# MCU.net
KiCad netlist of a schematic drawn in Altium Designer
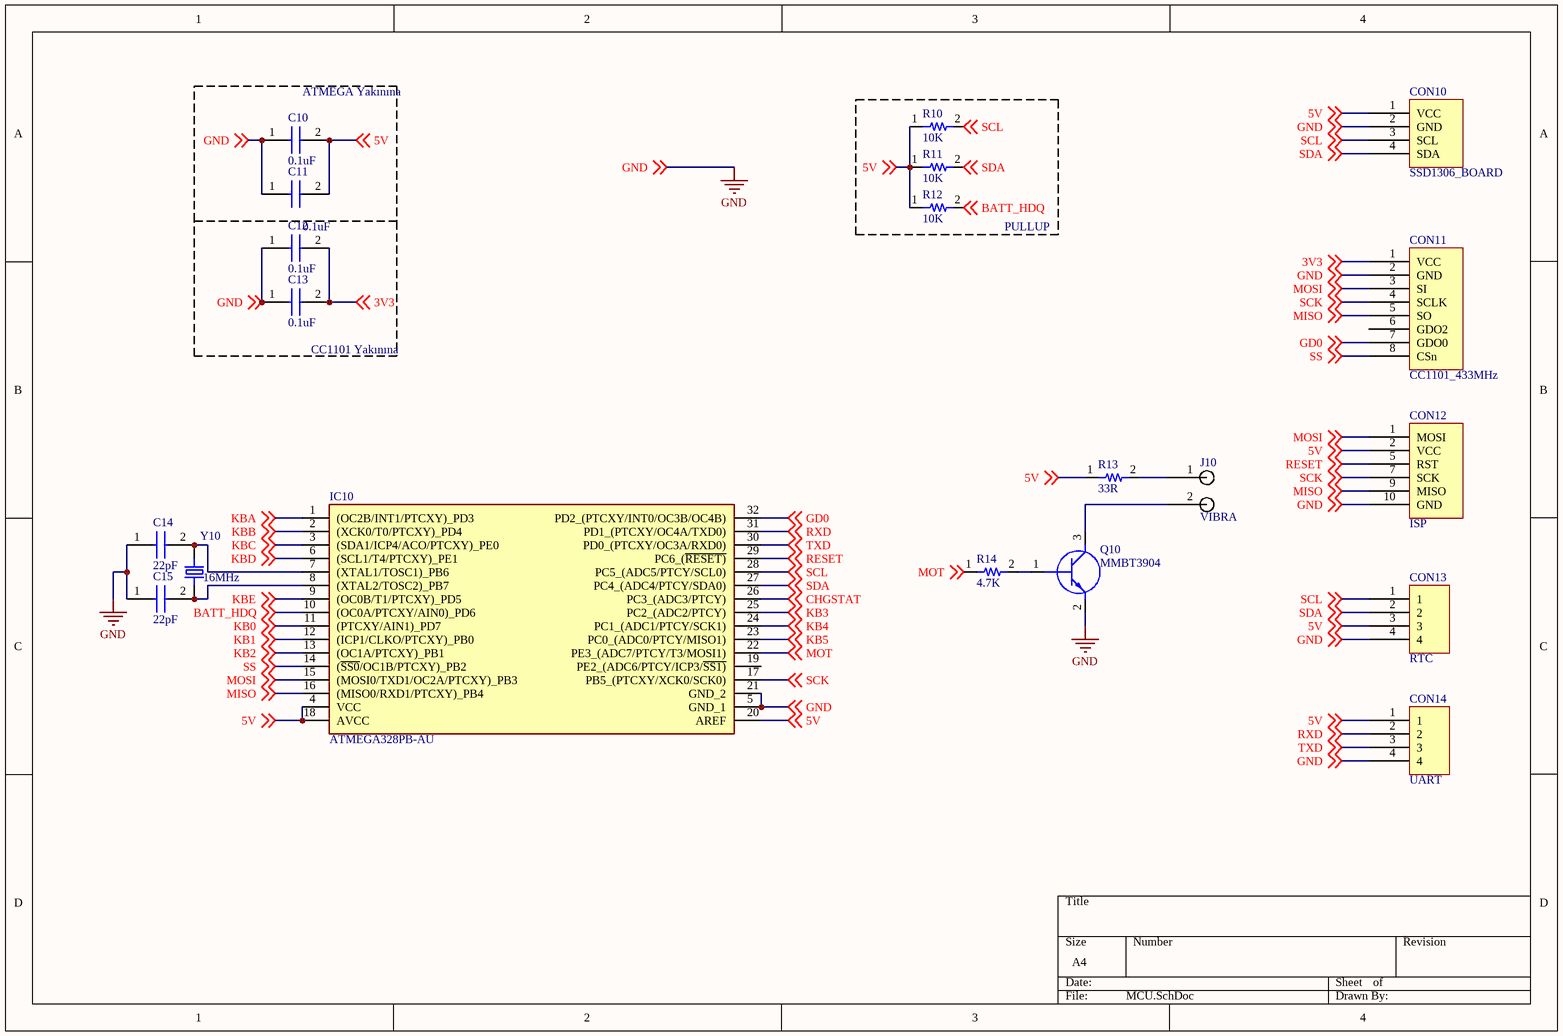
[diagram p0: MCU.SchDoc]

(export (version "E")
  (design (tool "Eeschema 10.0.6"))
  (components
    (comp (ref "C10")
      (value "0.1uF")
      (footprint "0603 Capacitor")
      (description "Capacitor")
      (fields
        (field (name "MANUFACTURER_PART_NUMBER") "06031A120JAT2A")
        (field (name "MOUSER PART NUMBER") "581-06031A120J")
      )
      (libsource (lib "uAltiumLib") (part "0603 Capacitor"))
    )
    (comp (ref "C11")
      (value "0.1uF")
      (footprint "0603 Capacitor")
      (description "Capacitor")
      (fields
        (field (name "MANUFACTURER_PART_NUMBER") "06031A120JAT2A")
        (field (name "MOUSER PART NUMBER") "581-06031A120J")
      )
      (libsource (lib "uAltiumLib") (part "0603 Capacitor"))
    )
    (comp (ref "C12")
      (value "0.1uF")
      (footprint "0603 Capacitor")
      (description "Capacitor")
      (fields
        (field (name "MANUFACTURER_PART_NUMBER") "06031A120JAT2A")
        (field (name "MOUSER PART NUMBER") "581-06031A120J")
      )
      (libsource (lib "uAltiumLib") (part "0603 Capacitor"))
    )
    (comp (ref "C13")
      (value "0.1uF")
      (footprint "0603 Capacitor")
      (description "Capacitor")
      (fields
        (field (name "MANUFACTURER_PART_NUMBER") "06031A120JAT2A")
        (field (name "MOUSER PART NUMBER") "581-06031A120J")
      )
      (libsource (lib "uAltiumLib") (part "0603 Capacitor"))
    )
    (comp (ref "C14")
      (value "22pF")
      (footprint "0603 Capacitor")
      (description "Capacitor")
      (fields
        (field (name "MANUFACTURER_PART_NUMBER") "06031A120JAT2A")
        (field (name "MOUSER PART NUMBER") "581-06031A120J")
      )
      (libsource (lib "uAltiumLib") (part "0603 Capacitor"))
    )
    (comp (ref "C15")
      (value "22pF")
      (footprint "0603 Capacitor")
      (description "Capacitor")
      (fields
        (field (name "MANUFACTURER_PART_NUMBER") "06031A120JAT2A")
        (field (name "MOUSER PART NUMBER") "581-06031A120J")
      )
      (libsource (lib "uAltiumLib") (part "0603 Capacitor"))
    )
    (comp (ref "CON10")
      (value "SSD1306_BOARD")
      (footprint "SSD1306_PCB")
      (libsource (lib "uAltiumLib") (part "SSD1306_BOARD"))
    )
    (comp (ref "CON11")
      (value "CC1101_433MHz")
      (footprint "CC1101_433MHz")
      (libsource (lib "uAltiumLib") (part "CC1101_433MHz"))
    )
    (comp (ref "CON12") (value "ISP") (footprint "ISP") (libsource (lib "uAltiumLib") (part "ISP")))
    (comp (ref "CON13")
      (value "RTC")
      (footprint "JumperHDR4")
      (libsource (lib "uAltiumLib") (part "JumperHDR4"))
    )
    (comp (ref "CON14")
      (value "UART")
      (footprint "JumperHDR4")
      (libsource (lib "uAltiumLib") (part "JumperHDR4"))
    )
    (comp (ref "IC10")
      (value "ATMEGA328PB-AU")
      (footprint "328PB-AU")
      (description "Integrated Circuit")
      (fields (field (name "MOUSER PART NUMBER") "556-ATMEGA328PB-AU"))
      (libsource (lib "uAltiumLib") (part "ATMEGA328PB-AU"))
    )
    (comp (ref "J10")
      (value "VIBRA")
      (footprint "JumperHDR")
      (libsource (lib "uAltiumLib") (part "JumperHDR_ALT"))
    )
    (comp (ref "Q10")
      (value "MMBT3904")
      (footprint "SamacSys:SOT95P240X120-3N")
      (description "Transistor BJT NPN")
      (fields (field (name "MOUSER PART NUMBER") "512-MMBT3904"))
      (libsource (lib "*") (part "MMBT3904"))
    )
    (comp (ref "R10")
      (value "10K")
      (footprint "0603 Resistor")
      (description "Resistor")
      (fields
        (field (name "MANUFACTURER_PART_NUMBER") "CPF0603B100RE1")
        (field (name "MOUSER PART NUMBER") "279-CPF0603B100RE1")
      )
      (libsource (lib "uAltiumLib") (part "0603 Resistor"))
    )
    (comp (ref "R11")
      (value "10K")
      (footprint "0603 Resistor")
      (description "Resistor")
      (fields
        (field (name "MANUFACTURER_PART_NUMBER") "CPF0603B100RE1")
        (field (name "MOUSER PART NUMBER") "279-CPF0603B100RE1")
      )
      (libsource (lib "uAltiumLib") (part "0603 Resistor"))
    )
    (comp (ref "R12")
      (value "10K")
      (footprint "0603 Resistor")
      (description "Resistor")
      (fields
        (field (name "MANUFACTURER_PART_NUMBER") "CPF0603B100RE1")
        (field (name "MOUSER PART NUMBER") "279-CPF0603B100RE1")
      )
      (libsource (lib "uAltiumLib") (part "0603 Resistor"))
    )
    (comp (ref "R13")
      (value "33R")
      (footprint "0603 Resistor")
      (description "Resistor")
      (fields
        (field (name "MANUFACTURER_PART_NUMBER") "CPF0603B100RE1")
        (field (name "MOUSER PART NUMBER") "279-CPF0603B100RE1")
      )
      (libsource (lib "uAltiumLib") (part "0603 Resistor"))
    )
    (comp (ref "R14")
      (value "4.7K")
      (footprint "0603 Resistor")
      (description "Resistor")
      (fields
        (field (name "MANUFACTURER_PART_NUMBER") "CPF0603B100RE1")
        (field (name "MOUSER PART NUMBER") "279-CPF0603B100RE1")
      )
      (libsource (lib "uAltiumLib") (part "0603 Resistor"))
    )
    (comp (ref "Y10")
      (value "16MHz")
      (footprint "Crystal-HC49")
      (fields
        (field (name "DIGI-KEY_PART_NUMBER") "X1115-ND")
        (field (name "MF") "ECS Inc.")
        (field (name "MP") "ECS-80-18-4XDN")
      )
      (libsource (lib "uAltiumLib") (part "HC49 Crystal"))
    )
  )
  (nets
    (net (code "1") (name "3V3") (class "Default")
      (node (ref "C12") (pin "2") (pinfunction "2_2") (pintype "passive"))
      (node (ref "C13") (pin "2") (pinfunction "2_2") (pintype "passive"))
      (node (ref "CON11") (pin "1") (pinfunction "VCC_1") (pintype "passive"))
    )
    (net (code "2") (name "5V") (class "Default")
      (node (ref "C10") (pin "2") (pinfunction "2_2") (pintype "passive"))
      (node (ref "C11") (pin "2") (pinfunction "2_2") (pintype "passive"))
      (node (ref "CON10") (pin "1") (pinfunction "VCC_1") (pintype "passive"))
      (node (ref "CON12") (pin "2") (pinfunction "VCC_2") (pintype "passive"))
      (node (ref "CON13") (pin "3") (pinfunction "3_3") (pintype "passive"))
      (node (ref "CON14") (pin "1") (pinfunction "1_1") (pintype "passive"))
      (node (ref "IC10") (pin "18") (pinfunction "AVCC_18") (pintype "passive"))
      (node (ref "IC10") (pin "20") (pinfunction "AREF_20") (pintype "passive"))
      (node (ref "IC10") (pin "4") (pinfunction "VCC_4") (pintype "passive"))
      (node (ref "R10") (pin "1") (pinfunction "1_1") (pintype "passive"))
      (node (ref "R11") (pin "1") (pinfunction "1_1") (pintype "passive"))
      (node (ref "R12") (pin "1") (pinfunction "1_1") (pintype "passive"))
      (node (ref "R13") (pin "1") (pinfunction "1_1") (pintype "passive"))
    )
    (net (code "3") (name "BATT_HDQ") (class "Default")
      (node (ref "IC10") (pin "10") (pinfunction "(OC0A/PTCXY/AIN0)_PD6_10") (pintype "passive"))
      (node (ref "R12") (pin "2") (pinfunction "2_2") (pintype "passive"))
    )
    (net (code "4") (name "CHGSTAT") (class "Default")
      (node (ref "IC10") (pin "26") (pinfunction "PC3_(ADC3/PTCY)_26") (pintype "passive"))
    )
    (net (code "5") (name "GD0") (class "Default")
      (node (ref "CON11") (pin "7") (pinfunction "GDO0_7") (pintype "passive"))
      (node (ref "IC10") (pin "32") (pinfunction "PD2_(PTCXY/INT0/OC3B/OC4B)_32") (pintype "passive"))
    )
    (net (code "6") (name "GND") (class "Default")
      (node (ref "C10") (pin "1") (pinfunction "1_1") (pintype "passive"))
      (node (ref "C11") (pin "1") (pinfunction "1_1") (pintype "passive"))
      (node (ref "C12") (pin "1") (pinfunction "1_1") (pintype "passive"))
      (node (ref "C13") (pin "1") (pinfunction "1_1") (pintype "passive"))
      (node (ref "C14") (pin "1") (pinfunction "1_1") (pintype "passive"))
      (node (ref "C15") (pin "1") (pinfunction "1_1") (pintype "passive"))
      (node (ref "CON10") (pin "2") (pinfunction "GND_2") (pintype "passive"))
      (node (ref "CON11") (pin "2") (pinfunction "GND_2") (pintype "passive"))
      (node (ref "CON12") (pin "10") (pinfunction "GND_10") (pintype "passive"))
      (node (ref "CON13") (pin "4") (pinfunction "4_4") (pintype "passive"))
      (node (ref "CON14") (pin "4") (pinfunction "4_4") (pintype "passive"))
      (node (ref "IC10") (pin "21") (pinfunction "GND_2_21") (pintype "passive"))
      (node (ref "IC10") (pin "5") (pinfunction "GND_1_5") (pintype "passive"))
      (node (ref "Q10") (pin "2") (pinfunction "E_2") (pintype "passive"))
    )
    (net (code "7") (name "KB0") (class "Default")
      (node (ref "IC10") (pin "11") (pinfunction "(PTCXY/AIN1)_PD7_11") (pintype "passive"))
    )
    (net (code "8") (name "KB1") (class "Default")
      (node (ref "IC10") (pin "12") (pinfunction "(ICP1/CLKO/PTCXY)_PB0_12") (pintype "passive"))
    )
    (net (code "9") (name "KB2") (class "Default")
      (node (ref "IC10") (pin "13") (pinfunction "(OC1A/PTCXY)_PB1_13") (pintype "passive"))
    )
    (net (code "10") (name "KB3") (class "Default")
      (node (ref "IC10") (pin "25") (pinfunction "PC2_(ADC2/PTCY)_25") (pintype "passive"))
    )
    (net (code "11") (name "KB4") (class "Default")
      (node (ref "IC10") (pin "24") (pinfunction "PC1_(ADC1/PTCY/SCK1)_24") (pintype "passive"))
    )
    (net (code "12") (name "KB5") (class "Default")
      (node (ref "IC10") (pin "23") (pinfunction "PC0_(ADC0/PTCY/MISO1)_23") (pintype "passive"))
    )
    (net (code "13") (name "KBA") (class "Default")
      (node (ref "IC10") (pin "1") (pinfunction "(OC2B/INT1/PTCXY)_PD3_1") (pintype "passive"))
    )
    (net (code "14") (name "KBB") (class "Default")
      (node (ref "IC10") (pin "2") (pinfunction "(XCK0/T0/PTCXY)_PD4_2") (pintype "passive"))
    )
    (net (code "15") (name "KBC") (class "Default")
      (node (ref "IC10") (pin "3") (pinfunction "(SDA1/ICP4/ACO/PTCXY)_PE0_3") (pintype "passive"))
    )
    (net (code "16") (name "KBD") (class "Default")
      (node (ref "IC10") (pin "6") (pinfunction "(SCL1/T4/PTCXY)_PE1_6") (pintype "passive"))
    )
    (net (code "17") (name "KBE") (class "Default")
      (node (ref "IC10") (pin "9") (pinfunction "(OC0B/T1/PTCXY)_PD5_9") (pintype "passive"))
    )
    (net (code "18") (name "MISO") (class "Default")
      (node (ref "CON11") (pin "5") (pinfunction "SO_5") (pintype "passive"))
      (node (ref "CON12") (pin "9") (pinfunction "MISO_9") (pintype "passive"))
      (node (ref "IC10") (pin "16") (pinfunction "(MISO0/RXD1/PTCXY)_PB4_16") (pintype "passive"))
    )
    (net (code "19") (name "MOSI") (class "Default")
      (node (ref "CON11") (pin "3") (pinfunction "SI_3") (pintype "passive"))
      (node (ref "CON12") (pin "1") (pinfunction "MOSI_1") (pintype "passive"))
      (node (ref "IC10") (pin "15") (pinfunction "(MOSI0/TXD1/OC2A/PTCXY)_PB3_15") (pintype "passive"))
    )
    (net (code "20") (name "MOT") (class "Default")
      (node (ref "IC10") (pin "22") (pinfunction "PE3_(ADC7/PTCY/T3/MOSI1)_22") (pintype "passive"))
      (node (ref "R14") (pin "1") (pinfunction "1_1") (pintype "passive"))
    )
    (net (code "21") (name "Net-(IC10-(XTAL1{slash}TOSC1)_PB6)") (class "Default")
      (node (ref "C14") (pin "2") (pinfunction "2_2") (pintype "passive"))
      (node (ref "IC10") (pin "7") (pinfunction "(XTAL1/TOSC1)_PB6_7") (pintype "passive"))
      (node (ref "Y10") (pin "2") (pinfunction "2_2") (pintype "passive"))
    )
    (net (code "22") (name "Net-(IC10-(XTAL2{slash}TOSC2)_PB7)") (class "Default")
      (node (ref "C15") (pin "2") (pinfunction "2_2") (pintype "passive"))
      (node (ref "IC10") (pin "8") (pinfunction "(XTAL2/TOSC2)_PB7_8") (pintype "passive"))
      (node (ref "Y10") (pin "1") (pinfunction "1_1") (pintype "passive"))
    )
    (net (code "23") (name "Net-(J10-Pad1)") (class "Default")
      (node (ref "J10") (pin "1") (pinfunction "1_1") (pintype "passive"))
      (node (ref "R13") (pin "2") (pinfunction "2_2") (pintype "passive"))
    )
    (net (code "24") (name "Net-(Q10-B)") (class "Default")
      (node (ref "Q10") (pin "1") (pinfunction "B_1") (pintype "passive"))
      (node (ref "R14") (pin "2") (pinfunction "2_2") (pintype "passive"))
    )
    (net (code "25") (name "Net-(Q10-C)") (class "Default")
      (node (ref "J10") (pin "2") (pinfunction "2_2") (pintype "passive"))
      (node (ref "Q10") (pin "3") (pinfunction "C_3") (pintype "passive"))
    )
    (net (code "26") (name "RESET") (class "Default")
      (node (ref "CON12") (pin "5") (pinfunction "RST_5") (pintype "passive"))
      (node (ref "IC10") (pin "29") (pinfunction "PC6_(~{RESET)}_29") (pintype "passive"))
    )
    (net (code "27") (name "RXD") (class "Default")
      (node (ref "CON14") (pin "2") (pinfunction "2_2") (pintype "passive"))
      (node (ref "IC10") (pin "31") (pinfunction "PD1_(PTCXY/OC4A/TXD0)_31") (pintype "passive"))
    )
    (net (code "28") (name "SCK") (class "Default")
      (node (ref "CON11") (pin "4") (pinfunction "SCLK_4") (pintype "passive"))
      (node (ref "CON12") (pin "7") (pinfunction "SCK_7") (pintype "passive"))
      (node (ref "IC10") (pin "17") (pinfunction "PB5_(PTCXY/XCK0/SCK0)_17") (pintype "passive"))
    )
    (net (code "29") (name "SCL") (class "Default")
      (node (ref "CON10") (pin "3") (pinfunction "SCL_3") (pintype "passive"))
      (node (ref "CON13") (pin "1") (pinfunction "1_1") (pintype "passive"))
      (node (ref "IC10") (pin "28") (pinfunction "PC5_(ADC5/PTCY/SCL0)_28") (pintype "passive"))
      (node (ref "R10") (pin "2") (pinfunction "2_2") (pintype "passive"))
    )
    (net (code "30") (name "SDA") (class "Default")
      (node (ref "CON10") (pin "4") (pinfunction "SDA_4") (pintype "passive"))
      (node (ref "CON13") (pin "2") (pinfunction "2_2") (pintype "passive"))
      (node (ref "IC10") (pin "27") (pinfunction "PC4_(ADC4/PTCY/SDA0)_27") (pintype "passive"))
      (node (ref "R11") (pin "2") (pinfunction "2_2") (pintype "passive"))
    )
    (net (code "31") (name "SS") (class "Default")
      (node (ref "CON11") (pin "8") (pinfunction "CSn_8") (pintype "passive"))
      (node (ref "IC10") (pin "14") (pinfunction "(~{SS0}/OC1B/PTCXY)_PB2_14") (pintype "passive"))
    )
    (net (code "32") (name "TXD") (class "Default")
      (node (ref "CON14") (pin "3") (pinfunction "3_3") (pintype "passive"))
      (node (ref "IC10") (pin "30") (pinfunction "PD0_(PTCXY/OC3A/RXD0)_30") (pintype "passive"))
    )
    (net (code "33") (name "unconnected-(CON11-GDO2-Pad6)") (class "Default")
      (node (ref "CON11") (pin "6") (pinfunction "GDO2_6") (pintype "passive"))
    )
    (net (code "34") (name "unconnected-(IC10-PE2_(ADC6{slash}PTCY{slash}ICP3{slash}~{SS1)}-Pad19)") (class "Default")
      (node (ref "IC10") (pin "19") (pinfunction "PE2_(ADC6/PTCY/ICP3/~{SS1)}_19") (pintype "passive"))
    )
  )
)
